# Transmitter_board.net
KiCad netlist of a schematic drawn in EAGLE
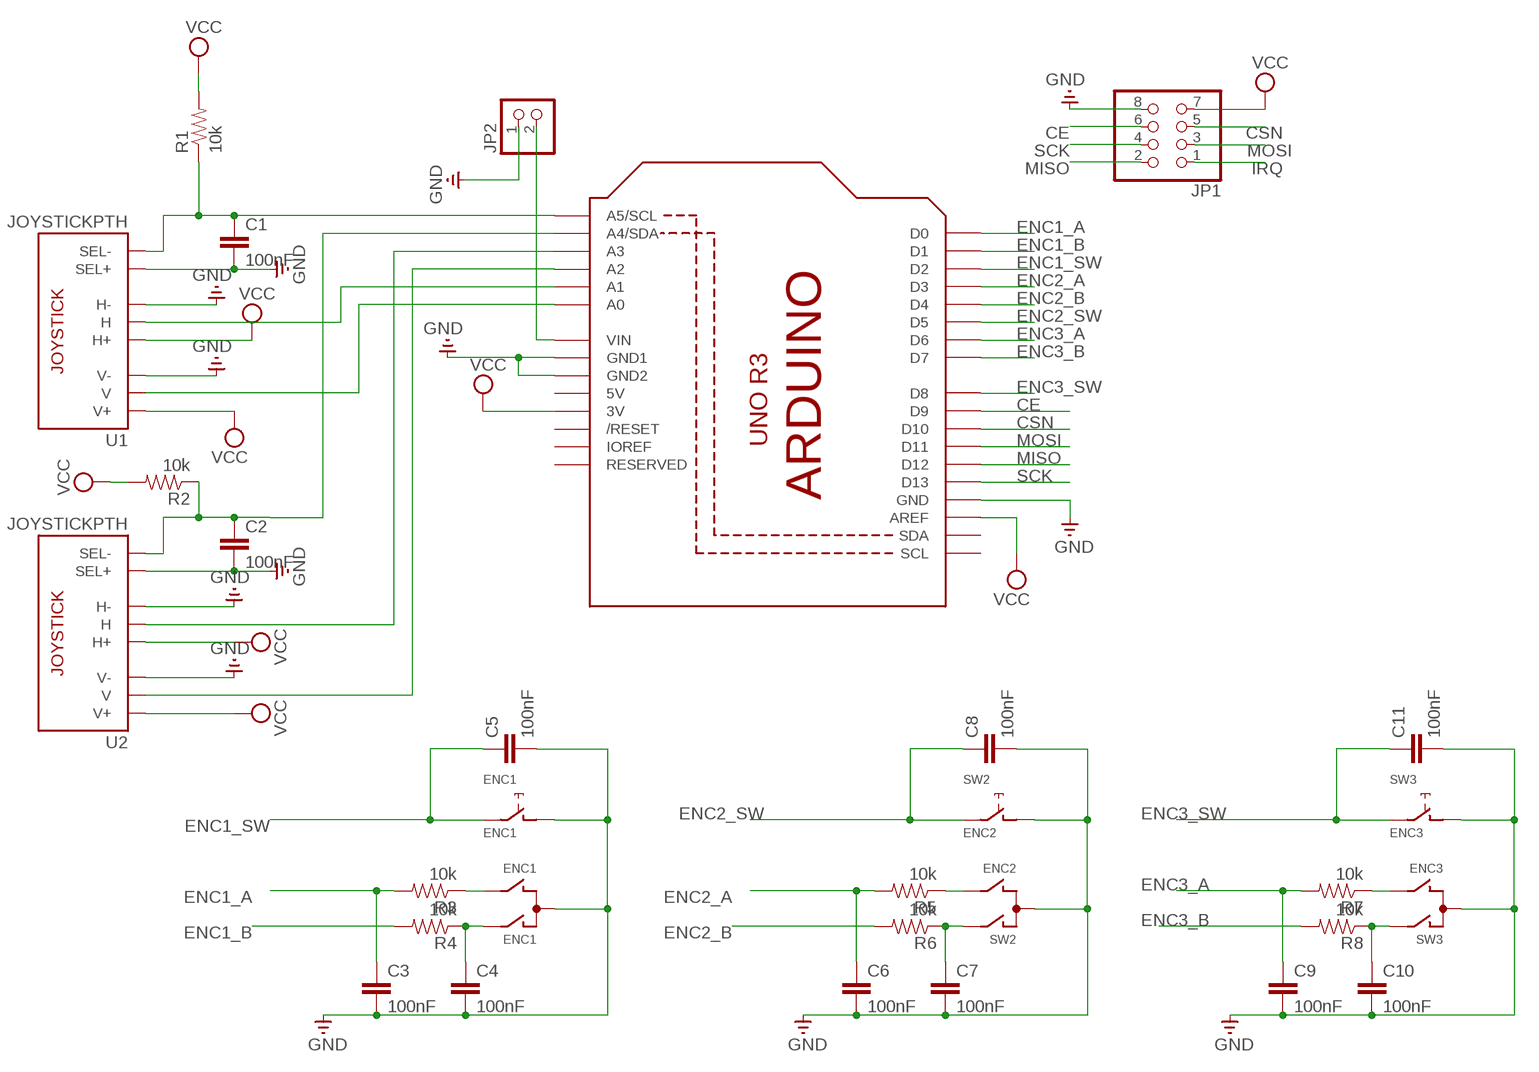
[diagram p0: schematic, sheet 1]

(export (version "E")
  (design (tool "Eeschema 10.0.6"))
  (components
    (comp (ref "C1")
      (value "100nF")
      (footprint "eagle-import:0603-CAP")
      (libsource (lib "eagle-import") (part "CAP0603-CAP"))
    )
    (comp (ref "C2")
      (value "100nF")
      (footprint "eagle-import:0603-CAP")
      (libsource (lib "eagle-import") (part "CAP0603-CAP"))
    )
    (comp (ref "C3")
      (value "100nF")
      (footprint "eagle-import:0603-CAP")
      (libsource (lib "eagle-import") (part "CAP0603-CAP"))
    )
    (comp (ref "C4")
      (value "100nF")
      (footprint "eagle-import:0603-CAP")
      (libsource (lib "eagle-import") (part "CAP0603-CAP"))
    )
    (comp (ref "C5")
      (value "100nF")
      (footprint "eagle-import:0603-CAP")
      (libsource (lib "eagle-import") (part "CAP0603-CAP"))
    )
    (comp (ref "C6")
      (value "100nF")
      (footprint "eagle-import:0603-CAP")
      (libsource (lib "eagle-import") (part "CAP0603-CAP"))
    )
    (comp (ref "C7")
      (value "100nF")
      (footprint "eagle-import:0603-CAP")
      (libsource (lib "eagle-import") (part "CAP0603-CAP"))
    )
    (comp (ref "C8")
      (value "100nF")
      (footprint "eagle-import:0603-CAP")
      (libsource (lib "eagle-import") (part "CAP0603-CAP"))
    )
    (comp (ref "C9")
      (value "100nF")
      (footprint "eagle-import:0603-CAP")
      (libsource (lib "eagle-import") (part "CAP0603-CAP"))
    )
    (comp (ref "C10")
      (value "100nF")
      (footprint "eagle-import:0603-CAP")
      (libsource (lib "eagle-import") (part "CAP0603-CAP"))
    )
    (comp (ref "C11")
      (value "100nF")
      (footprint "eagle-import:0603-CAP")
      (libsource (lib "eagle-import") (part "CAP0603-CAP"))
    )
    (comp (ref "ENC1")
      (value "ENC1")
      (footprint "eagle-import:ALPS_EC12E_SW")
      (fields (field (name "MPN") "EC12E2424407"))
      (libsource (lib "eagle-import") (part "EC12E_SW"))
    )
    (comp (ref "JP1")
      (value "PINHD-2X4")
      (footprint "eagle-import:2X04")
      (libsource (lib "eagle-import") (part "PINHD-2X4"))
    )
    (comp (ref "JP2")
      (value "PINHD-1X2")
      (footprint "eagle-import:1X02")
      (libsource (lib "eagle-import") (part "PINHD-1X2"))
    )
    (comp (ref "R1")
      (value "10k")
      (footprint "eagle-import:0603-RES")
      (libsource (lib "eagle-import") (part "RESISTOR0603-RES"))
    )
    (comp (ref "R2")
      (value "10k")
      (footprint "eagle-import:0603-RES")
      (libsource (lib "eagle-import") (part "RESISTOR0603-RES"))
    )
    (comp (ref "R3")
      (value "10k")
      (footprint "eagle-import:0603-RES")
      (libsource (lib "eagle-import") (part "RESISTOR0603-RES"))
    )
    (comp (ref "R4")
      (value "10k")
      (footprint "eagle-import:0603-RES")
      (libsource (lib "eagle-import") (part "RESISTOR0603-RES"))
    )
    (comp (ref "R5")
      (value "10k")
      (footprint "eagle-import:0603-RES")
      (libsource (lib "eagle-import") (part "RESISTOR0603-RES"))
    )
    (comp (ref "R6")
      (value "10k")
      (footprint "eagle-import:0603-RES")
      (libsource (lib "eagle-import") (part "RESISTOR0603-RES"))
    )
    (comp (ref "R7")
      (value "10k")
      (footprint "eagle-import:0603-RES")
      (libsource (lib "eagle-import") (part "RESISTOR0603-RES"))
    )
    (comp (ref "R8")
      (value "10k")
      (footprint "eagle-import:0603-RES")
      (libsource (lib "eagle-import") (part "RESISTOR0603-RES"))
    )
    (comp (ref "SW2")
      (value "ENC2")
      (footprint "eagle-import:ALPS_EC12E_SW")
      (fields (field (name "MPN") "EC12E2424407"))
      (libsource (lib "eagle-import") (part "EC12E_SW"))
    )
    (comp (ref "SW3")
      (value "ENC3")
      (footprint "eagle-import:ALPS_EC12E_SW")
      (fields (field (name "MPN") "EC12E2424407"))
      (libsource (lib "eagle-import") (part "EC12E_SW"))
    )
    (comp (ref "U1")
      (value "JOYSTICKPTH")
      (footprint "eagle-import:JOYSTICK")
      (libsource (lib "eagle-import") (part "JOYSTICKPTH"))
    )
    (comp (ref "U2")
      (value "JOYSTICKPTH")
      (footprint "eagle-import:JOYSTICK")
      (libsource (lib "eagle-import") (part "JOYSTICKPTH"))
    )
    (comp (ref "U3")
      (value "STM32F746NG")
      (footprint "eagle-import:ARDUINOR3-BPLACE")
      (libsource (lib "eagle-import") (part "ARDUINOR3-BPLACE"))
    )
  )
  (nets
    (net (code "1") (name "/5V") (class "Default")
      (node (ref "U3") (pin "5V") (pinfunction "5V_5V") (pintype "power_in"))
    )
    (net (code "2") (name "/CE") (class "Default")
      (node (ref "JP1") (pin "6") (pinfunction "6_6") (pintype "passive"))
      (node (ref "U3") (pin "D9") (pinfunction "D9_D9") (pintype "bidirectional"))
    )
    (net (code "3") (name "/CSN") (class "Default")
      (node (ref "JP1") (pin "5") (pinfunction "5_5") (pintype "passive"))
      (node (ref "U3") (pin "D10") (pinfunction "D10_D10") (pintype "bidirectional"))
    )
    (net (code "4") (name "/ENC1_A") (class "Default")
      (node (ref "C3") (pin "1") (pinfunction "1_1") (pintype "passive"))
      (node (ref "R3") (pin "2") (pinfunction "2_2") (pintype "passive"))
      (node (ref "U3") (pin "D0") (pinfunction "D0_D0") (pintype "bidirectional"))
    )
    (net (code "5") (name "/ENC1_B") (class "Default")
      (node (ref "R4") (pin "2") (pinfunction "2_2") (pintype "passive"))
      (node (ref "U3") (pin "D1") (pinfunction "D1_D1") (pintype "bidirectional"))
    )
    (net (code "6") (name "/ENC1_SW") (class "Default")
      (node (ref "C5") (pin "1") (pinfunction "1_1") (pintype "passive"))
      (node (ref "ENC1") (pin "E") (pinfunction "2_E") (pintype "passive"))
      (node (ref "U3") (pin "D2") (pinfunction "D2_D2") (pintype "bidirectional"))
    )
    (net (code "7") (name "/ENC2_A") (class "Default")
      (node (ref "C6") (pin "1") (pinfunction "1_1") (pintype "passive"))
      (node (ref "R5") (pin "2") (pinfunction "2_2") (pintype "passive"))
      (node (ref "U3") (pin "D3") (pinfunction "D3_D3") (pintype "bidirectional"))
    )
    (net (code "8") (name "/ENC2_B") (class "Default")
      (node (ref "R6") (pin "2") (pinfunction "2_2") (pintype "passive"))
      (node (ref "U3") (pin "D4") (pinfunction "D4_D4") (pintype "bidirectional"))
    )
    (net (code "9") (name "/ENC2_SW") (class "Default")
      (node (ref "C8") (pin "1") (pinfunction "1_1") (pintype "passive"))
      (node (ref "SW2") (pin "E") (pinfunction "2_E") (pintype "passive"))
      (node (ref "U3") (pin "D5") (pinfunction "D5_D5") (pintype "bidirectional"))
    )
    (net (code "10") (name "/ENC3_A") (class "Default")
      (node (ref "C9") (pin "1") (pinfunction "1_1") (pintype "passive"))
      (node (ref "R7") (pin "2") (pinfunction "2_2") (pintype "passive"))
      (node (ref "U3") (pin "D6") (pinfunction "D6_D6") (pintype "bidirectional"))
    )
    (net (code "11") (name "/ENC3_B") (class "Default")
      (node (ref "R8") (pin "2") (pinfunction "2_2") (pintype "passive"))
      (node (ref "U3") (pin "D7") (pinfunction "D7_D7") (pintype "bidirectional"))
    )
    (net (code "12") (name "/ENC3_SW") (class "Default")
      (node (ref "C11") (pin "1") (pinfunction "1_1") (pintype "passive"))
      (node (ref "SW3") (pin "E") (pinfunction "2_E") (pintype "passive"))
      (node (ref "U3") (pin "D8") (pinfunction "D8_D8") (pintype "bidirectional"))
    )
    (net (code "13") (name "/IRQ") (class "Default")
      (node (ref "JP1") (pin "1") (pinfunction "1_1") (pintype "passive"))
    )
    (net (code "14") (name "/MISO") (class "Default")
      (node (ref "JP1") (pin "2") (pinfunction "2_2") (pintype "passive"))
      (node (ref "U3") (pin "D12") (pinfunction "D12_D12") (pintype "bidirectional"))
    )
    (net (code "15") (name "/MOSI") (class "Default")
      (node (ref "JP1") (pin "3") (pinfunction "3_3") (pintype "passive"))
      (node (ref "U3") (pin "D11") (pinfunction "D11_D11") (pintype "bidirectional"))
    )
    (net (code "16") (name "/SCK") (class "Default")
      (node (ref "JP1") (pin "4") (pinfunction "4_4") (pintype "passive"))
      (node (ref "U3") (pin "D13") (pinfunction "D13_D13") (pintype "bidirectional"))
    )
    (net (code "17") (name "GND") (class "Default")
      (node (ref "C1") (pin "2") (pinfunction "2_2") (pintype "passive"))
      (node (ref "C10") (pin "2") (pinfunction "2_2") (pintype "passive"))
      (node (ref "C11") (pin "2") (pinfunction "2_2") (pintype "passive"))
      (node (ref "C2") (pin "2") (pinfunction "2_2") (pintype "passive"))
      (node (ref "C3") (pin "2") (pinfunction "2_2") (pintype "passive"))
      (node (ref "C4") (pin "2") (pinfunction "2_2") (pintype "passive"))
      (node (ref "C5") (pin "2") (pinfunction "2_2") (pintype "passive"))
      (node (ref "C6") (pin "2") (pinfunction "2_2") (pintype "passive"))
      (node (ref "C7") (pin "2") (pinfunction "2_2") (pintype "passive"))
      (node (ref "C8") (pin "2") (pinfunction "2_2") (pintype "passive"))
      (node (ref "C9") (pin "2") (pinfunction "2_2") (pintype "passive"))
      (node (ref "ENC1") (pin "C") (pinfunction "C_C") (pintype "passive"))
      (node (ref "ENC1") (pin "D") (pinfunction "1_D") (pintype "passive"))
      (node (ref "JP1") (pin "8") (pinfunction "8_8") (pintype "passive"))
      (node (ref "JP2") (pin "1") (pinfunction "1_1") (pintype "passive"))
      (node (ref "SW2") (pin "C") (pinfunction "C_C") (pintype "passive"))
      (node (ref "SW2") (pin "D") (pinfunction "1_D") (pintype "passive"))
      (node (ref "SW3") (pin "C") (pinfunction "C_C") (pintype "passive"))
      (node (ref "SW3") (pin "D") (pinfunction "1_D") (pintype "passive"))
      (node (ref "U1") (pin "B1A") (pinfunction "SEL+_B1A") (pintype "bidirectional"))
      (node (ref "U1") (pin "H3") (pinfunction "H-_H3") (pintype "bidirectional"))
      (node (ref "U1") (pin "V3") (pinfunction "V-_V3") (pintype "bidirectional"))
      (node (ref "U2") (pin "B1A") (pinfunction "SEL+_B1A") (pintype "bidirectional"))
      (node (ref "U2") (pin "H3") (pinfunction "H-_H3") (pintype "bidirectional"))
      (node (ref "U2") (pin "V3") (pinfunction "V-_V3") (pintype "bidirectional"))
      (node (ref "U3") (pin "GND") (pinfunction "GND_GND") (pintype "power_in"))
      (node (ref "U3") (pin "GND1") (pinfunction "GND1_GND1") (pintype "power_in"))
      (node (ref "U3") (pin "GND2") (pinfunction "GND2_GND2") (pintype "power_in"))
    )
    (net (code "18") (name "Net-(C4-Pad1)") (class "Default")
      (node (ref "C4") (pin "1") (pinfunction "1_1") (pintype "passive"))
      (node (ref "ENC1") (pin "A") (pinfunction "A_A") (pintype "passive"))
      (node (ref "R4") (pin "1") (pinfunction "1_1") (pintype "passive"))
    )
    (net (code "19") (name "Net-(C7-Pad1)") (class "Default")
      (node (ref "C7") (pin "1") (pinfunction "1_1") (pintype "passive"))
      (node (ref "R6") (pin "1") (pinfunction "1_1") (pintype "passive"))
      (node (ref "SW2") (pin "A") (pinfunction "A_A") (pintype "passive"))
    )
    (net (code "20") (name "Net-(C10-Pad1)") (class "Default")
      (node (ref "C10") (pin "1") (pinfunction "1_1") (pintype "passive"))
      (node (ref "R8") (pin "1") (pinfunction "1_1") (pintype "passive"))
      (node (ref "SW3") (pin "A") (pinfunction "A_A") (pintype "passive"))
    )
    (net (code "21") (name "Net-(ENC1-PadB)") (class "Default")
      (node (ref "ENC1") (pin "B") (pinfunction "B_B") (pintype "passive"))
      (node (ref "R3") (pin "1") (pinfunction "1_1") (pintype "passive"))
    )
    (net (code "22") (name "Net-(JP2-Pad2)") (class "Default")
      (node (ref "JP2") (pin "2") (pinfunction "2_2") (pintype "passive"))
      (node (ref "U3") (pin "VIN") (pinfunction "VIN_VIN") (pintype "power_in"))
    )
    (net (code "23") (name "Net-(R5-Pad1)") (class "Default")
      (node (ref "R5") (pin "1") (pinfunction "1_1") (pintype "passive"))
      (node (ref "SW2") (pin "B") (pinfunction "B_B") (pintype "passive"))
    )
    (net (code "24") (name "Net-(R7-Pad1)") (class "Default")
      (node (ref "R7") (pin "1") (pinfunction "1_1") (pintype "passive"))
      (node (ref "SW3") (pin "B") (pinfunction "B_B") (pintype "passive"))
    )
    (net (code "25") (name "Net-(U1-H)") (class "Default")
      (node (ref "U1") (pin "H2") (pinfunction "H_H2") (pintype "bidirectional"))
      (node (ref "U3") (pin "A1") (pinfunction "A1_A1") (pintype "bidirectional"))
    )
    (net (code "26") (name "Net-(U1-SEL-)") (class "Default")
      (node (ref "C1") (pin "1") (pinfunction "1_1") (pintype "passive"))
      (node (ref "R1") (pin "1") (pinfunction "1_1") (pintype "passive"))
      (node (ref "U1") (pin "B2A") (pinfunction "SEL-_B2A") (pintype "bidirectional"))
      (node (ref "U3") (pin "A5") (pinfunction "A5/SCL_A5") (pintype "bidirectional"))
    )
    (net (code "27") (name "Net-(U1-V)") (class "Default")
      (node (ref "U1") (pin "V2") (pinfunction "V_V2") (pintype "bidirectional"))
      (node (ref "U3") (pin "A0") (pinfunction "A0_A0") (pintype "bidirectional"))
    )
    (net (code "28") (name "Net-(U2-H)") (class "Default")
      (node (ref "U2") (pin "H2") (pinfunction "H_H2") (pintype "bidirectional"))
      (node (ref "U3") (pin "A3") (pinfunction "A3_A3") (pintype "bidirectional"))
    )
    (net (code "29") (name "Net-(U2-SEL-)") (class "Default")
      (node (ref "C2") (pin "1") (pinfunction "1_1") (pintype "passive"))
      (node (ref "R2") (pin "1") (pinfunction "1_1") (pintype "passive"))
      (node (ref "U2") (pin "B2A") (pinfunction "SEL-_B2A") (pintype "bidirectional"))
      (node (ref "U3") (pin "A4") (pinfunction "A4/SDA_A4") (pintype "bidirectional"))
    )
    (net (code "30") (name "Net-(U2-V)") (class "Default")
      (node (ref "U2") (pin "V2") (pinfunction "V_V2") (pintype "bidirectional"))
      (node (ref "U3") (pin "A2") (pinfunction "A2_A2") (pintype "bidirectional"))
    )
    (net (code "31") (name "VCC") (class "Default")
      (node (ref "JP1") (pin "7") (pinfunction "7_7") (pintype "passive"))
      (node (ref "R1") (pin "2") (pinfunction "2_2") (pintype "passive"))
      (node (ref "R2") (pin "2") (pinfunction "2_2") (pintype "passive"))
      (node (ref "U1") (pin "H1") (pinfunction "H+_H1") (pintype "bidirectional"))
      (node (ref "U1") (pin "V1") (pinfunction "V+_V1") (pintype "bidirectional"))
      (node (ref "U2") (pin "H1") (pinfunction "H+_H1") (pintype "bidirectional"))
      (node (ref "U2") (pin "V1") (pinfunction "V+_V1") (pintype "bidirectional"))
      (node (ref "U3") (pin "3V") (pinfunction "3V_3V") (pintype "power_in"))
      (node (ref "U3") (pin "AREF") (pinfunction "AREF_AREF") (pintype "bidirectional"))
    )
    (net (code "32") (name "unconnected-(U3-PadIOREF)") (class "Default")
      (node (ref "U3") (pin "IOREF") (pinfunction "IOREF_IOREF") (pintype "output"))
    )
    (net (code "33") (name "unconnected-(U3-PadRESERVED)") (class "Default")
      (node (ref "U3") (pin "RESERVED") (pinfunction "RESERVED_RESERVED") (pintype "no_connect"))
    )
    (net (code "34") (name "unconnected-(U3-PadSCL)") (class "Default")
      (node (ref "U3") (pin "SCL") (pinfunction "SCL_SCL") (pintype "bidirectional"))
    )
    (net (code "35") (name "unconnected-(U3-PadSDA)") (class "Default")
      (node (ref "U3") (pin "SDA") (pinfunction "SDA_SDA") (pintype "bidirectional"))
    )
    (net (code "36") (name "unconnected-(U3-{slash}RESET-PadRESET)") (class "Default")
      (node (ref "U3") (pin "RESET") (pinfunction "/RESET_RESET") (pintype "bidirectional"))
    )
  )
)
